# BLE_torch_v1_0.net
KiCad netlist of a schematic drawn in EAGLE
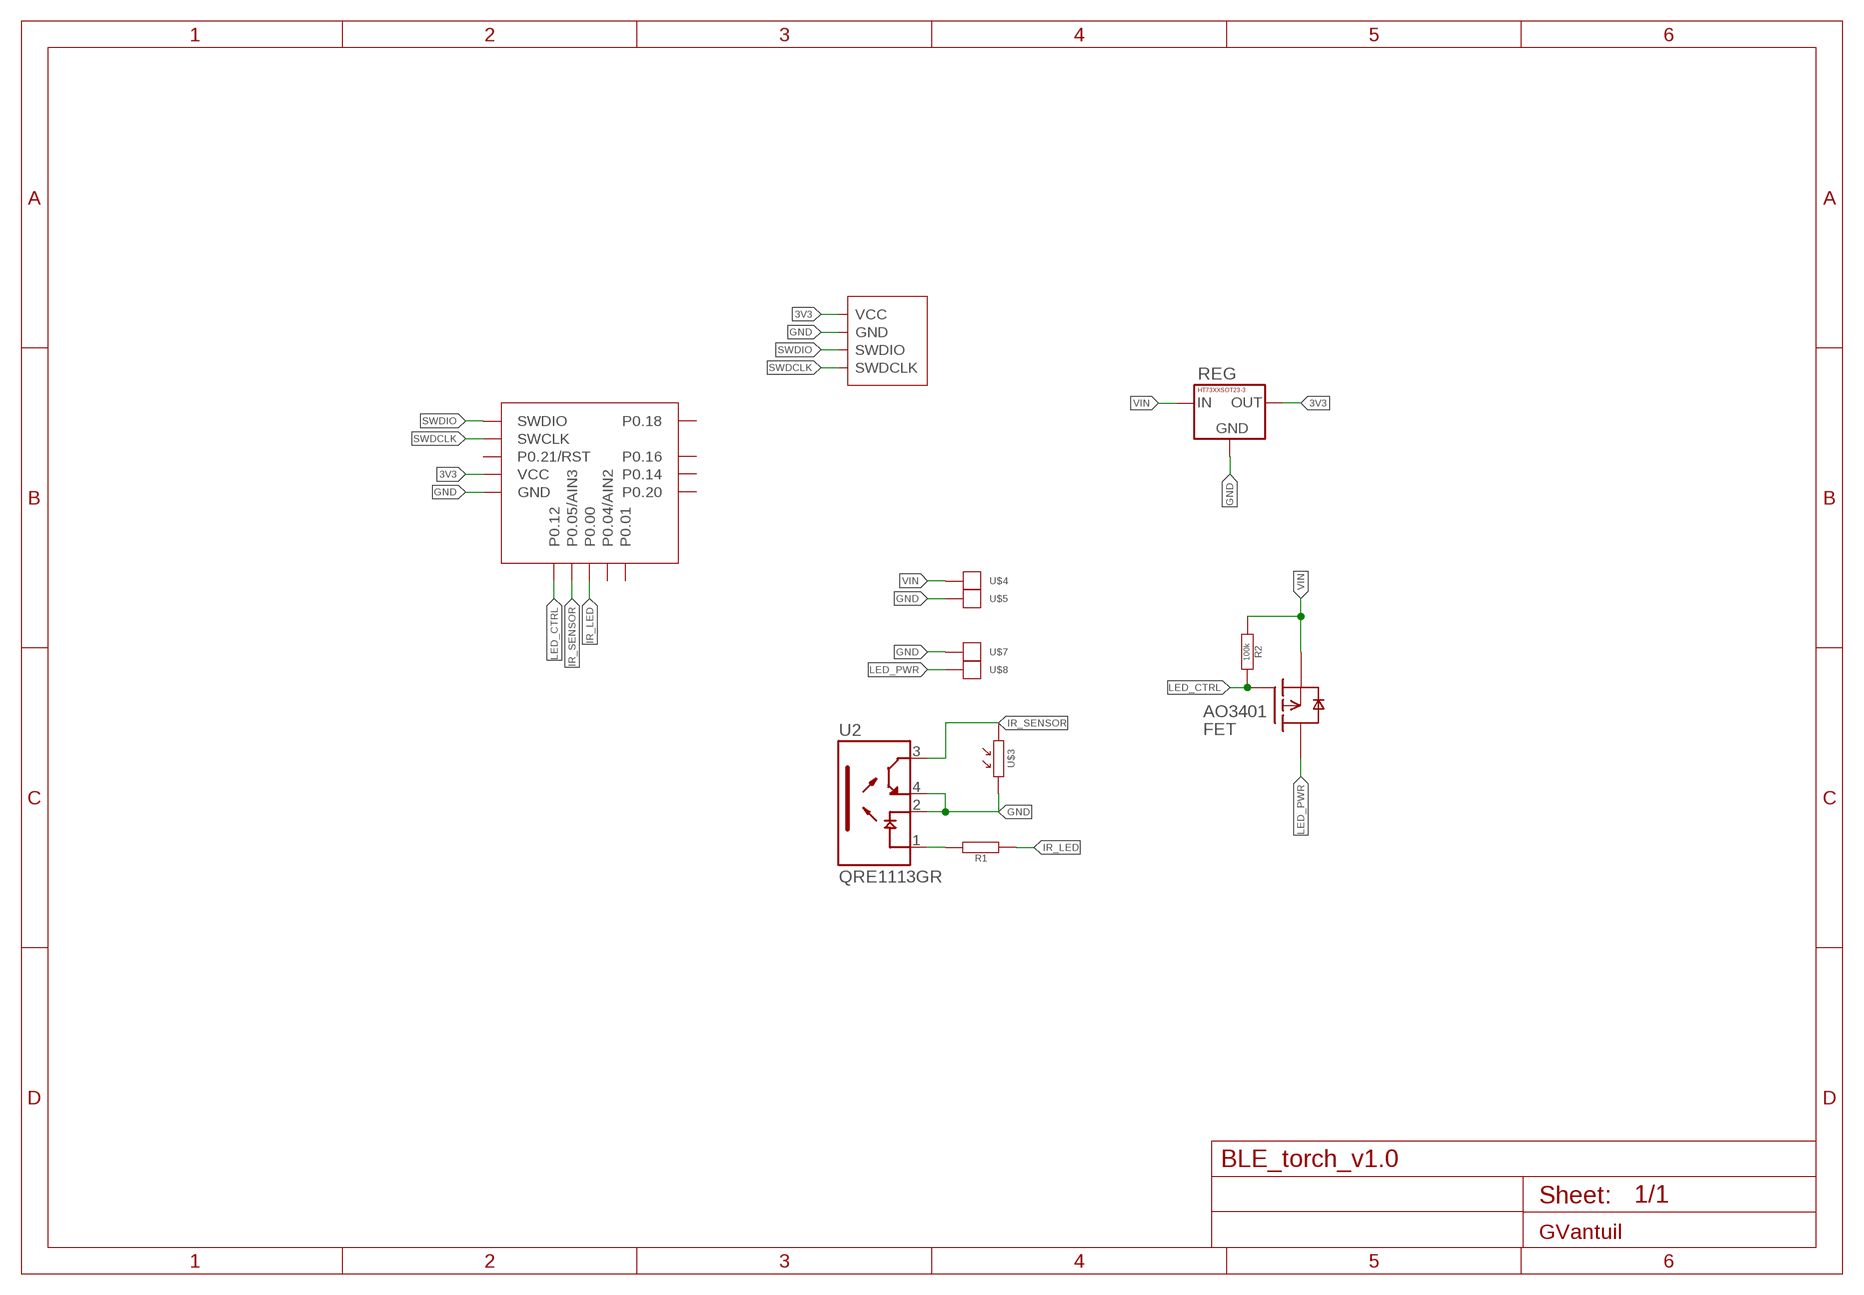
[diagram p0: schematic, sheet 1]

(export (version "E")
  (design (tool "Eeschema 10.0.6"))
  (components
    (comp (ref "FET")
      (value "AO3401")
      (footprint "eagle-import:SOT23-3")
      (fields (field (name "MF") "Alpha & Omega Semiconductor"))
      (libsource (lib "eagle-import") (part "AO3401"))
    )
    (comp (ref "R1")
      (value "RESISTOR0402-RES")
      (footprint "eagle-import:0402-RES")
      (libsource (lib "eagle-import") (part "RESISTOR0402-RES"))
    )
    (comp (ref "R2")
      (value "100k")
      (footprint "eagle-import:0402-RES")
      (libsource (lib "eagle-import") (part "RESISTOR0402-RES"))
    )
    (comp (ref "REG")
      (value "HT73XXSOT23-3")
      (footprint "eagle-import:SOT23-3")
      (libsource (lib "eagle-import") (part "HT73XXSOT23-3"))
    )
    (comp (ref "U$2")
      (value "E104-BT5005A")
      (footprint "eagle-import:E104-BT5005A")
      (libsource (lib "eagle-import") (part "E104-BT5005A"))
    )
    (comp (ref "U$3")
      (value "LDR_5MM")
      (footprint "eagle-import:LDR_5MM")
      (libsource (lib "eagle-import") (part "LDR_5MM"))
    )
    (comp (ref "U$4")
      (value "PAD_50X100MIL")
      (footprint "eagle-import:PAD_50X100MIL")
      (libsource (lib "eagle-import") (part "PAD_50X100MIL"))
    )
    (comp (ref "U$5")
      (value "PAD_50X100MIL")
      (footprint "eagle-import:PAD_50X100MIL")
      (libsource (lib "eagle-import") (part "PAD_50X100MIL"))
    )
    (comp (ref "U$6")
      (value "GV_SWD_4P")
      (footprint "eagle-import:GV_SWD_1.27MM_4P_SEMI_SMD")
      (libsource (lib "eagle-import") (part "GV_SWD_4P"))
    )
    (comp (ref "U$7")
      (value "PAD_1.3X5MM")
      (footprint "eagle-import:PAD_1.3X5MM")
      (libsource (lib "eagle-import") (part "PAD_1.3X5MM"))
    )
    (comp (ref "U$8")
      (value "PAD_1.3X5MM")
      (footprint "eagle-import:PAD_1.3X5MM")
      (libsource (lib "eagle-import") (part "PAD_1.3X5MM"))
    )
    (comp (ref "U2")
      (value "QRE1113GR")
      (footprint "eagle-import:SOIC180P460X187-4N")
      (fields (field (name "MF") "ON Semiconductor"))
      (libsource (lib "eagle-import") (part "QRE1113GR"))
    )
  )
  (nets
    (net (code "1") (name "3V3") (class "Default")
      (node (ref "REG") (pin "2") (pinfunction "3.OUT_2") (pintype "bidirectional"))
      (node (ref "U$2") (pin "VCC") (pinfunction "VCC_VCC") (pintype "bidirectional"))
      (node (ref "U$6") (pin "VCC") (pinfunction "VCC_VCC") (pintype "bidirectional"))
    )
    (net (code "2") (name "GND") (class "Default")
      (node (ref "REG") (pin "1") (pinfunction "2.GND_1") (pintype "input"))
      (node (ref "U$2") (pin "GND") (pinfunction "GND_GND") (pintype "bidirectional"))
      (node (ref "U$2") (pin "GND1") (pinfunction "GND_GND1") (pintype "bidirectional"))
      (node (ref "U$3") (pin "P$1") (pinfunction "P$1_P$1") (pintype "bidirectional"))
      (node (ref "U$5") (pin "P$1") (pinfunction "P$1_P$1") (pintype "bidirectional"))
      (node (ref "U$6") (pin "GND") (pinfunction "GND_GND") (pintype "bidirectional"))
      (node (ref "U$7") (pin "P$1") (pinfunction "P$1_P$1") (pintype "bidirectional"))
      (node (ref "U2") (pin "2") (pinfunction "C_2") (pintype "passive"))
      (node (ref "U2") (pin "4") (pinfunction "ET_4") (pintype "passive"))
    )
    (net (code "3") (name "IR_LED") (class "Default")
      (node (ref "R1") (pin "1") (pinfunction "1_1") (pintype "passive"))
      (node (ref "U$2") (pin "P0.00") (pinfunction "P0.00_P0.00") (pintype "bidirectional"))
    )
    (net (code "4") (name "IR_SENSOR") (class "Default")
      (node (ref "U$2") (pin "P0.05") (pinfunction "P0.05/AIN3_P0.05") (pintype "bidirectional"))
      (node (ref "U$3") (pin "P$2") (pinfunction "P$2_P$2") (pintype "bidirectional"))
      (node (ref "U2") (pin "3") (pinfunction "CT_3") (pintype "passive"))
    )
    (net (code "5") (name "LED_CTRL") (class "Default")
      (node (ref "FET") (pin "1") (pinfunction "G_1") (pintype "passive"))
      (node (ref "R2") (pin "2") (pinfunction "2_2") (pintype "passive"))
      (node (ref "U$2") (pin "P0.12") (pinfunction "P0.12_P0.12") (pintype "bidirectional"))
    )
    (net (code "6") (name "LED_PWR") (class "Default")
      (node (ref "FET") (pin "3") (pinfunction "D_3") (pintype "passive"))
      (node (ref "U$8") (pin "P$1") (pinfunction "P$1_P$1") (pintype "bidirectional"))
    )
    (net (code "7") (name "Net-(U2-A)") (class "Default")
      (node (ref "R1") (pin "2") (pinfunction "2_2") (pintype "passive"))
      (node (ref "U2") (pin "1") (pinfunction "A_1") (pintype "passive"))
    )
    (net (code "8") (name "SWDCLK") (class "Default")
      (node (ref "U$2") (pin "SWCLK") (pinfunction "SWCLK_SWCLK") (pintype "bidirectional"))
      (node (ref "U$6") (pin "SWDCLK") (pinfunction "SWDCLK_SWDCLK") (pintype "bidirectional"))
    )
    (net (code "9") (name "SWDIO") (class "Default")
      (node (ref "U$2") (pin "SWDIO") (pinfunction "SWDIO_SWDIO") (pintype "bidirectional"))
      (node (ref "U$6") (pin "SWDIO") (pinfunction "SWDIO_SWDIO") (pintype "bidirectional"))
    )
    (net (code "10") (name "VIN") (class "Default")
      (node (ref "FET") (pin "2") (pinfunction "S_2") (pintype "passive"))
      (node (ref "R2") (pin "1") (pinfunction "1_1") (pintype "passive"))
      (node (ref "REG") (pin "3") (pinfunction "1.IN_3") (pintype "input"))
      (node (ref "U$4") (pin "P$1") (pinfunction "P$1_P$1") (pintype "bidirectional"))
    )
    (net (code "11") (name "unconnected-(U$2-P0.04{slash}AIN2-PadP0.04)") (class "Default")
      (node (ref "U$2") (pin "P0.04") (pinfunction "P0.04/AIN2_P0.04") (pintype "bidirectional"))
    )
    (net (code "12") (name "unconnected-(U$2-PadP0.01)") (class "Default")
      (node (ref "U$2") (pin "P0.01") (pinfunction "P0.01_P0.01") (pintype "bidirectional"))
    )
    (net (code "13") (name "unconnected-(U$2-PadP0.14)") (class "Default")
      (node (ref "U$2") (pin "P0.14") (pinfunction "P0.14_P0.14") (pintype "bidirectional"))
    )
    (net (code "14") (name "unconnected-(U$2-PadP0.16)") (class "Default")
      (node (ref "U$2") (pin "P0.16") (pinfunction "P0.16_P0.16") (pintype "bidirectional"))
    )
    (net (code "15") (name "unconnected-(U$2-PadP0.18)") (class "Default")
      (node (ref "U$2") (pin "P0.18") (pinfunction "P0.18_P0.18") (pintype "bidirectional"))
    )
    (net (code "16") (name "unconnected-(U$2-PadP0.20)") (class "Default")
      (node (ref "U$2") (pin "P0.20") (pinfunction "P0.20_P0.20") (pintype "bidirectional"))
    )
    (net (code "17") (name "unconnected-(U$2-PadP0.21{slash}RST)") (class "Default")
      (node (ref "U$2") (pin "P0.21/RST") (pinfunction "P0.21/RST_P0.21/RST") (pintype "bidirectional"))
    )
  )
)
